# caffeine-hardware.net
KiCad netlist of a schematic drawn in EAGLE
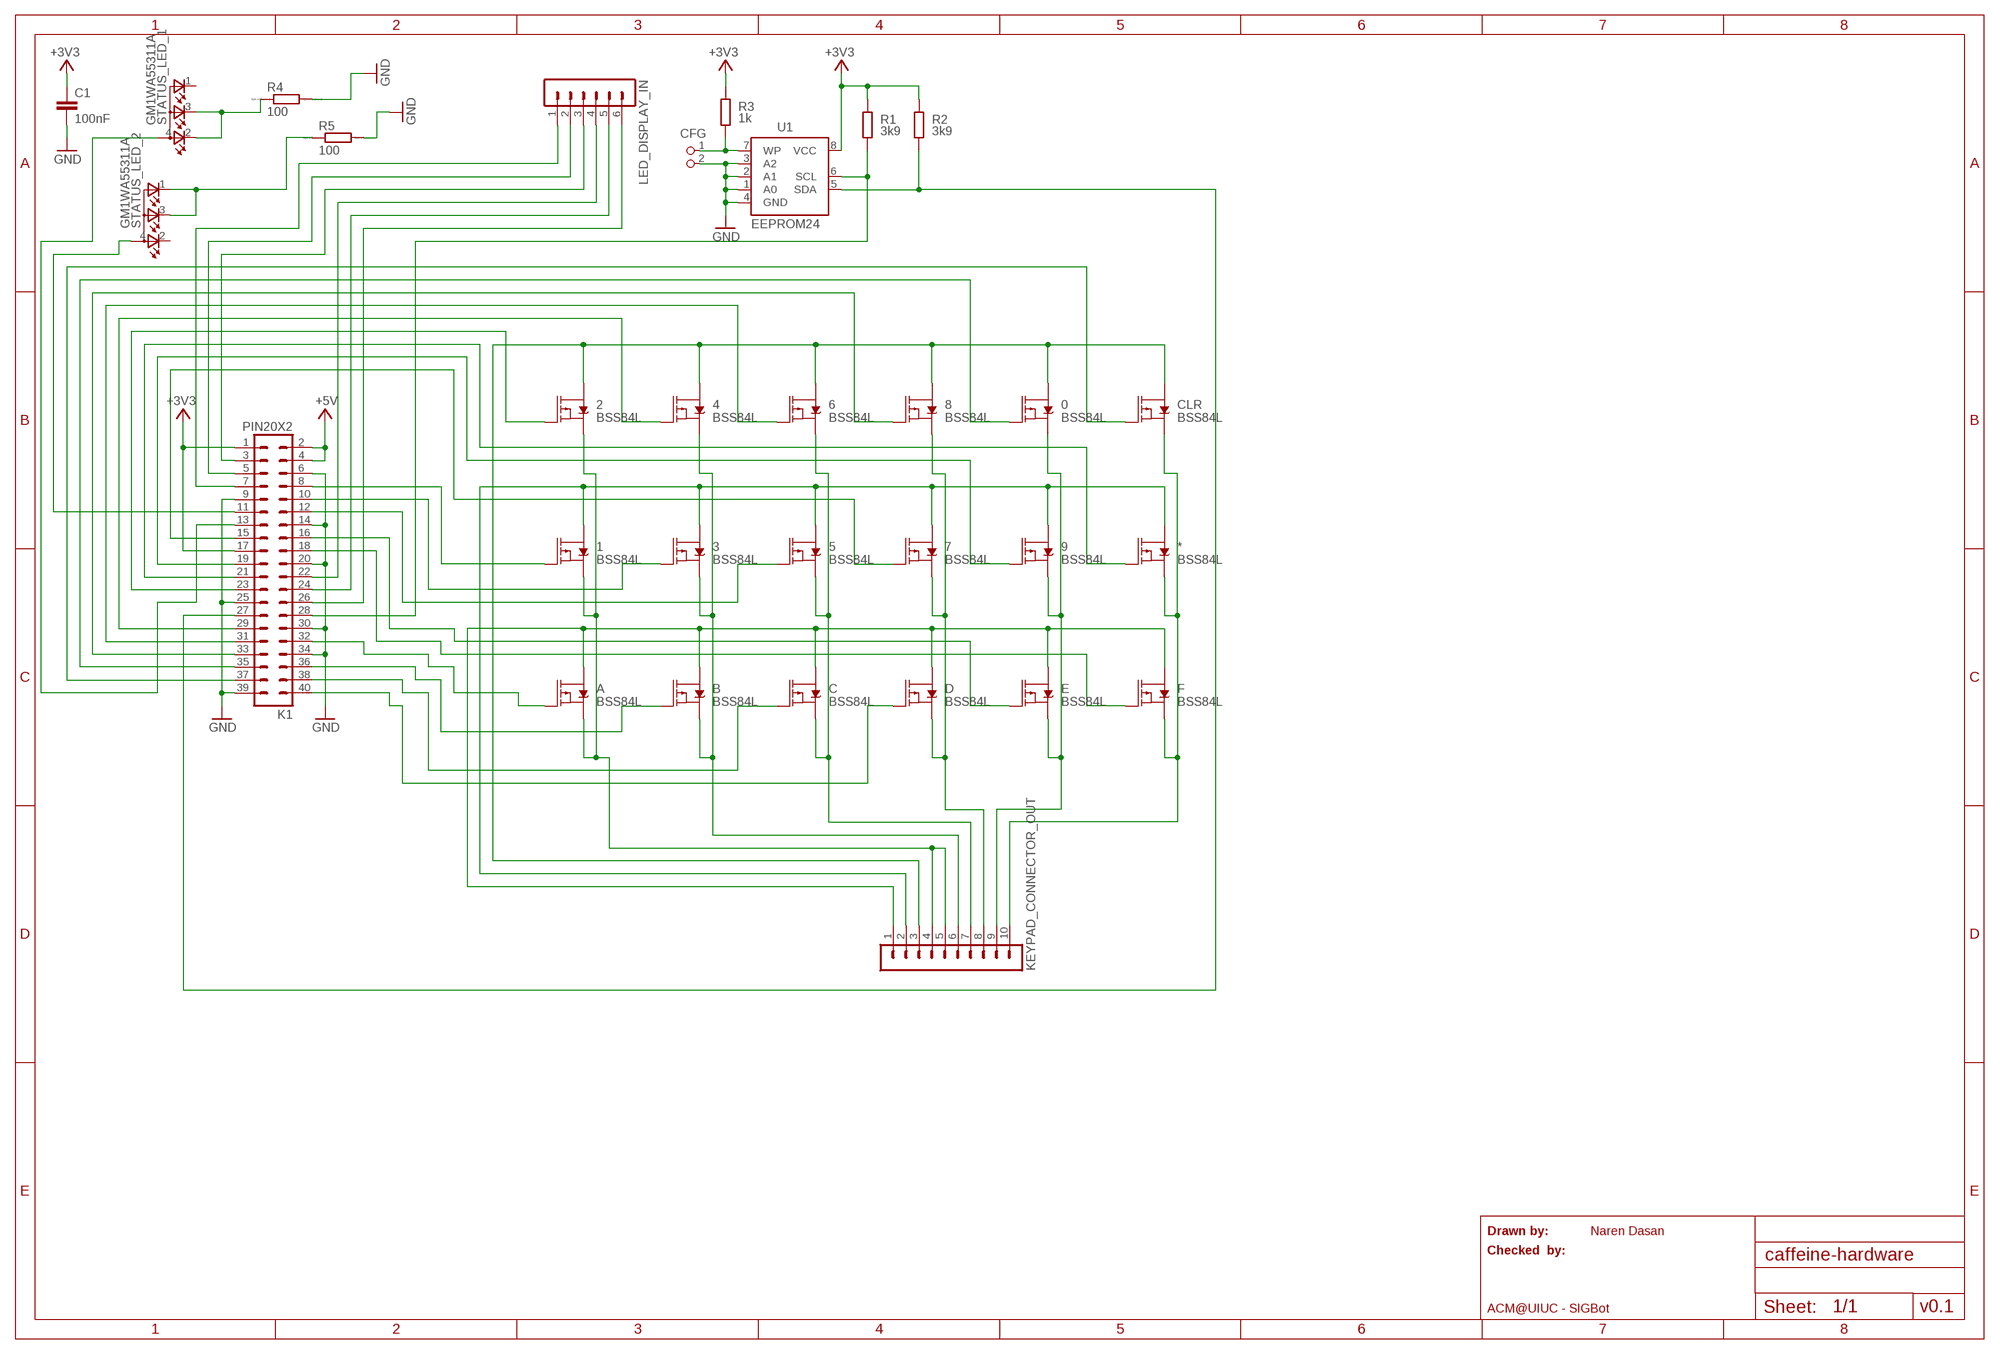
[diagram p0: schematic, sheet 1]

(export (version "E")
  (design (tool "Eeschema 10.0.6"))
  (components
    (comp (ref "*")
      (value "BSS84L")
      (footprint "eagle-import:SOT23-3")
      (libsource (lib "eagle-import") (part "MOSFET-PCH-SI2309DS"))
    )
    (comp (ref "0")
      (value "BSS84L")
      (footprint "eagle-import:SOT23-3")
      (libsource (lib "eagle-import") (part "MOSFET-PCH-SI2309DS"))
    )
    (comp (ref "1")
      (value "BSS84L")
      (footprint "eagle-import:SOT23-3")
      (libsource (lib "eagle-import") (part "MOSFET-PCH-SI2309DS"))
    )
    (comp (ref "2")
      (value "BSS84L")
      (footprint "eagle-import:SOT23-3")
      (libsource (lib "eagle-import") (part "MOSFET-PCH-SI2309DS"))
    )
    (comp (ref "3")
      (value "BSS84L")
      (footprint "eagle-import:SOT23-3")
      (libsource (lib "eagle-import") (part "MOSFET-PCH-SI2309DS"))
    )
    (comp (ref "4")
      (value "BSS84L")
      (footprint "eagle-import:SOT23-3")
      (libsource (lib "eagle-import") (part "MOSFET-PCH-SI2309DS"))
    )
    (comp (ref "5")
      (value "BSS84L")
      (footprint "eagle-import:SOT23-3")
      (libsource (lib "eagle-import") (part "MOSFET-PCH-SI2309DS"))
    )
    (comp (ref "6")
      (value "BSS84L")
      (footprint "eagle-import:SOT23-3")
      (libsource (lib "eagle-import") (part "MOSFET-PCH-SI2309DS"))
    )
    (comp (ref "7")
      (value "BSS84L")
      (footprint "eagle-import:SOT23-3")
      (libsource (lib "eagle-import") (part "MOSFET-PCH-SI2309DS"))
    )
    (comp (ref "8")
      (value "BSS84L")
      (footprint "eagle-import:SOT23-3")
      (libsource (lib "eagle-import") (part "MOSFET-PCH-SI2309DS"))
    )
    (comp (ref "9")
      (value "BSS84L")
      (footprint "eagle-import:SOT23-3")
      (libsource (lib "eagle-import") (part "MOSFET-PCH-SI2309DS"))
    )
    (comp (ref "A")
      (value "BSS84L")
      (footprint "eagle-import:SOT23-3")
      (libsource (lib "eagle-import") (part "MOSFET-PCH-SI2309DS"))
    )
    (comp (ref "B")
      (value "BSS84L")
      (footprint "eagle-import:SOT23-3")
      (libsource (lib "eagle-import") (part "MOSFET-PCH-SI2309DS"))
    )
    (comp (ref "C")
      (value "BSS84L")
      (footprint "eagle-import:SOT23-3")
      (libsource (lib "eagle-import") (part "MOSFET-PCH-SI2309DS"))
    )
    (comp (ref "C1")
      (value "100nF")
      (footprint "eagle-import:C0805K")
      (libsource (lib "eagle-import") (part "C-EUC0805K"))
    )
    (comp (ref "CFG")
      (value "PIN2_100")
      (footprint "eagle-import:PIN_W_2")
      (libsource (lib "eagle-import") (part "PIN2_100"))
    )
    (comp (ref "CLR")
      (value "BSS84L")
      (footprint "eagle-import:SOT23-3")
      (libsource (lib "eagle-import") (part "MOSFET-PCH-SI2309DS"))
    )
    (comp (ref "D")
      (value "BSS84L")
      (footprint "eagle-import:SOT23-3")
      (libsource (lib "eagle-import") (part "MOSFET-PCH-SI2309DS"))
    )
    (comp (ref "E")
      (value "BSS84L")
      (footprint "eagle-import:SOT23-3")
      (libsource (lib "eagle-import") (part "MOSFET-PCH-SI2309DS"))
    )
    (comp (ref "F")
      (value "BSS84L")
      (footprint "eagle-import:SOT23-3")
      (libsource (lib "eagle-import") (part "MOSFET-PCH-SI2309DS"))
    )
    (comp (ref "K1")
      (value "PIN20X2")
      (footprint "eagle-import:PIN_20X2")
      (libsource (lib "eagle-import") (part "PIN20X2"))
    )
    (comp (ref "KEYPAD_CONNECTOR_OUT")
      (value "MA10-1")
      (footprint "eagle-import:MA10-1")
      (libsource (lib "eagle-import") (part "MA10-1"))
    )
    (comp (ref "LED_DISPLAY_IN")
      (value "MA06-1")
      (footprint "eagle-import:MA06-1")
      (libsource (lib "eagle-import") (part "MA06-1"))
    )
    (comp (ref "R1")
      (value "3k9")
      (footprint "eagle-import:M0805")
      (fields (field (name "TOLERANCE") "5%"))
      (libsource (lib "eagle-import") (part "R-EU_M0805"))
    )
    (comp (ref "R2")
      (value "3k9")
      (footprint "eagle-import:M0805")
      (fields (field (name "TOLERANCE") "5%"))
      (libsource (lib "eagle-import") (part "R-EU_M0805"))
    )
    (comp (ref "R3")
      (value "1k")
      (footprint "eagle-import:M0805")
      (fields (field (name "TOLERANCE") "5%"))
      (libsource (lib "eagle-import") (part "R-EU_M0805"))
    )
    (comp (ref "R4")
      (value "100")
      (footprint "eagle-import:R0805")
      (libsource (lib "eagle-import") (part "R"))
    )
    (comp (ref "R5")
      (value "100")
      (footprint "eagle-import:R0805")
      (libsource (lib "eagle-import") (part "R"))
    )
    (comp (ref "STATUS_LED_1")
      (value "GM1WA55311A")
      (footprint "eagle-import:GM1WA55311A")
      (libsource (lib "eagle-import") (part "GM1WA55311A"))
    )
    (comp (ref "STATUS_LED_2")
      (value "GM1WA55311A")
      (footprint "eagle-import:GM1WA55311A")
      (libsource (lib "eagle-import") (part "GM1WA55311A"))
    )
    (comp (ref "U1")
      (value "EEPROM24")
      (footprint "eagle-import:SOIC8")
      (libsource (lib "eagle-import") (part "EEPROM24"))
    )
  )
  (nets
    (net (code "1") (name "+3V3") (class "Default")
      (node (ref "C1") (pin "1") (pinfunction "1_1") (pintype "passive"))
      (node (ref "K1") (pin "1") (pinfunction "1_1") (pintype "passive"))
      (node (ref "K1") (pin "17") (pinfunction "17_17") (pintype "passive"))
      (node (ref "R1") (pin "2") (pinfunction "2_2") (pintype "passive"))
      (node (ref "R2") (pin "2") (pinfunction "2_2") (pintype "passive"))
      (node (ref "R3") (pin "2") (pinfunction "2_2") (pintype "passive"))
      (node (ref "U1") (pin "8") (pinfunction "VCC_8") (pintype "power_in"))
    )
    (net (code "2") (name "+5V") (class "Default")
      (node (ref "K1") (pin "2") (pinfunction "2_2") (pintype "passive"))
      (node (ref "K1") (pin "4") (pinfunction "4_4") (pintype "passive"))
    )
    (net (code "3") (name "GND") (class "Default")
      (node (ref "C1") (pin "2") (pinfunction "2_2") (pintype "passive"))
      (node (ref "CFG") (pin "2") (pinfunction "2_2") (pintype "passive"))
      (node (ref "K1") (pin "14") (pinfunction "14_14") (pintype "passive"))
      (node (ref "K1") (pin "20") (pinfunction "20_20") (pintype "passive"))
      (node (ref "K1") (pin "25") (pinfunction "25_25") (pintype "passive"))
      (node (ref "K1") (pin "30") (pinfunction "30_30") (pintype "passive"))
      (node (ref "K1") (pin "34") (pinfunction "34_34") (pintype "passive"))
      (node (ref "K1") (pin "39") (pinfunction "39_39") (pintype "passive"))
      (node (ref "K1") (pin "6") (pinfunction "6_6") (pintype "passive"))
      (node (ref "K1") (pin "9") (pinfunction "9_9") (pintype "passive"))
      (node (ref "R4") (pin "2") (pinfunction "2_2") (pintype "passive"))
      (node (ref "R5") (pin "2") (pinfunction "2_2") (pintype "passive"))
      (node (ref "U1") (pin "1") (pinfunction "A0_1") (pintype "input"))
      (node (ref "U1") (pin "2") (pinfunction "A1_2") (pintype "input"))
      (node (ref "U1") (pin "3") (pinfunction "A2_3") (pintype "input"))
      (node (ref "U1") (pin "4") (pinfunction "GND_4") (pintype "power_in"))
    )
    (net (code "4") (name "Net-(*-D)") (class "Default")
      (node (ref "*") (pin "3") (pinfunction "D_3") (pintype "bidirectional"))
      (node (ref "1") (pin "3") (pinfunction "D_3") (pintype "bidirectional"))
      (node (ref "3") (pin "3") (pinfunction "D_3") (pintype "bidirectional"))
      (node (ref "5") (pin "3") (pinfunction "D_3") (pintype "bidirectional"))
      (node (ref "7") (pin "3") (pinfunction "D_3") (pintype "bidirectional"))
      (node (ref "9") (pin "3") (pinfunction "D_3") (pintype "bidirectional"))
      (node (ref "KEYPAD_CONNECTOR_OUT") (pin "2") (pinfunction "2_2") (pintype "passive"))
    )
    (net (code "5") (name "Net-(*-G)") (class "Default")
      (node (ref "*") (pin "1") (pinfunction "G_1") (pintype "bidirectional"))
      (node (ref "K1") (pin "21") (pinfunction "21_21") (pintype "passive"))
    )
    (net (code "6") (name "Net-(*-S)") (class "Default")
      (node (ref "*") (pin "2") (pinfunction "S_2") (pintype "bidirectional"))
      (node (ref "CLR") (pin "2") (pinfunction "S_2") (pintype "bidirectional"))
      (node (ref "F") (pin "2") (pinfunction "S_2") (pintype "bidirectional"))
      (node (ref "KEYPAD_CONNECTOR_OUT") (pin "10") (pinfunction "10_10") (pintype "passive"))
    )
    (net (code "7") (name "Net-(0-D)") (class "Default")
      (node (ref "0") (pin "3") (pinfunction "D_3") (pintype "bidirectional"))
      (node (ref "2") (pin "3") (pinfunction "D_3") (pintype "bidirectional"))
      (node (ref "4") (pin "3") (pinfunction "D_3") (pintype "bidirectional"))
      (node (ref "6") (pin "3") (pinfunction "D_3") (pintype "bidirectional"))
      (node (ref "8") (pin "3") (pinfunction "D_3") (pintype "bidirectional"))
      (node (ref "CLR") (pin "3") (pinfunction "D_3") (pintype "bidirectional"))
      (node (ref "KEYPAD_CONNECTOR_OUT") (pin "3") (pinfunction "3_3") (pintype "passive"))
    )
    (net (code "8") (name "Net-(0-G)") (class "Default")
      (node (ref "0") (pin "1") (pinfunction "G_1") (pintype "bidirectional"))
      (node (ref "K1") (pin "35") (pinfunction "35_35") (pintype "passive"))
    )
    (net (code "9") (name "Net-(0-S)") (class "Default")
      (node (ref "0") (pin "2") (pinfunction "S_2") (pintype "bidirectional"))
      (node (ref "9") (pin "2") (pinfunction "S_2") (pintype "bidirectional"))
      (node (ref "E") (pin "2") (pinfunction "S_2") (pintype "bidirectional"))
      (node (ref "KEYPAD_CONNECTOR_OUT") (pin "9") (pinfunction "9_9") (pintype "passive"))
    )
    (net (code "10") (name "Net-(1-G)") (class "Default")
      (node (ref "1") (pin "1") (pinfunction "G_1") (pintype "bidirectional"))
      (node (ref "K1") (pin "8") (pinfunction "8_8") (pintype "passive"))
    )
    (net (code "11") (name "Net-(1-S)") (class "Default")
      (node (ref "1") (pin "2") (pinfunction "S_2") (pintype "bidirectional"))
      (node (ref "2") (pin "2") (pinfunction "S_2") (pintype "bidirectional"))
      (node (ref "A") (pin "2") (pinfunction "S_2") (pintype "bidirectional"))
      (node (ref "KEYPAD_CONNECTOR_OUT") (pin "4") (pinfunction "4_4") (pintype "passive"))
      (node (ref "KEYPAD_CONNECTOR_OUT") (pin "5") (pinfunction "5_5") (pintype "passive"))
    )
    (net (code "12") (name "Net-(2-G)") (class "Default")
      (node (ref "2") (pin "1") (pinfunction "G_1") (pintype "bidirectional"))
      (node (ref "K1") (pin "23") (pinfunction "23_23") (pintype "passive"))
    )
    (net (code "13") (name "Net-(3-G)") (class "Default")
      (node (ref "3") (pin "1") (pinfunction "G_1") (pintype "bidirectional"))
      (node (ref "K1") (pin "10") (pinfunction "10_10") (pintype "passive"))
    )
    (net (code "14") (name "Net-(3-S)") (class "Default")
      (node (ref "3") (pin "2") (pinfunction "S_2") (pintype "bidirectional"))
      (node (ref "4") (pin "2") (pinfunction "S_2") (pintype "bidirectional"))
      (node (ref "B") (pin "2") (pinfunction "S_2") (pintype "bidirectional"))
      (node (ref "KEYPAD_CONNECTOR_OUT") (pin "6") (pinfunction "6_6") (pintype "passive"))
    )
    (net (code "15") (name "Net-(4-G)") (class "Default")
      (node (ref "4") (pin "1") (pinfunction "G_1") (pintype "bidirectional"))
      (node (ref "K1") (pin "29") (pinfunction "29_29") (pintype "passive"))
    )
    (net (code "16") (name "Net-(5-G)") (class "Default")
      (node (ref "5") (pin "1") (pinfunction "G_1") (pintype "bidirectional"))
      (node (ref "K1") (pin "12") (pinfunction "12_12") (pintype "passive"))
    )
    (net (code "17") (name "Net-(5-S)") (class "Default")
      (node (ref "5") (pin "2") (pinfunction "S_2") (pintype "bidirectional"))
      (node (ref "6") (pin "2") (pinfunction "S_2") (pintype "bidirectional"))
      (node (ref "C") (pin "2") (pinfunction "S_2") (pintype "bidirectional"))
      (node (ref "KEYPAD_CONNECTOR_OUT") (pin "7") (pinfunction "7_7") (pintype "passive"))
    )
    (net (code "18") (name "Net-(6-G)") (class "Default")
      (node (ref "6") (pin "1") (pinfunction "G_1") (pintype "bidirectional"))
      (node (ref "K1") (pin "31") (pinfunction "31_31") (pintype "passive"))
    )
    (net (code "19") (name "Net-(7-G)") (class "Default")
      (node (ref "7") (pin "1") (pinfunction "G_1") (pintype "bidirectional"))
      (node (ref "K1") (pin "15") (pinfunction "15_15") (pintype "passive"))
    )
    (net (code "20") (name "Net-(7-S)") (class "Default")
      (node (ref "7") (pin "2") (pinfunction "S_2") (pintype "bidirectional"))
      (node (ref "8") (pin "2") (pinfunction "S_2") (pintype "bidirectional"))
      (node (ref "D") (pin "2") (pinfunction "S_2") (pintype "bidirectional"))
      (node (ref "KEYPAD_CONNECTOR_OUT") (pin "8") (pinfunction "8_8") (pintype "passive"))
    )
    (net (code "21") (name "Net-(8-G)") (class "Default")
      (node (ref "8") (pin "1") (pinfunction "G_1") (pintype "bidirectional"))
      (node (ref "K1") (pin "33") (pinfunction "33_33") (pintype "passive"))
    )
    (net (code "22") (name "Net-(9-G)") (class "Default")
      (node (ref "9") (pin "1") (pinfunction "G_1") (pintype "bidirectional"))
      (node (ref "K1") (pin "19") (pinfunction "19_19") (pintype "passive"))
    )
    (net (code "23") (name "Net-(A-D)") (class "Default")
      (node (ref "A") (pin "3") (pinfunction "D_3") (pintype "bidirectional"))
      (node (ref "B") (pin "3") (pinfunction "D_3") (pintype "bidirectional"))
      (node (ref "C") (pin "3") (pinfunction "D_3") (pintype "bidirectional"))
      (node (ref "D") (pin "3") (pinfunction "D_3") (pintype "bidirectional"))
      (node (ref "E") (pin "3") (pinfunction "D_3") (pintype "bidirectional"))
      (node (ref "F") (pin "3") (pinfunction "D_3") (pintype "bidirectional"))
      (node (ref "KEYPAD_CONNECTOR_OUT") (pin "1") (pinfunction "1_1") (pintype "passive"))
    )
    (net (code "24") (name "Net-(A-G)") (class "Default")
      (node (ref "A") (pin "1") (pinfunction "G_1") (pintype "bidirectional"))
      (node (ref "K1") (pin "32") (pinfunction "32_32") (pintype "passive"))
    )
    (net (code "25") (name "Net-(B-G)") (class "Default")
      (node (ref "B") (pin "1") (pinfunction "G_1") (pintype "bidirectional"))
      (node (ref "K1") (pin "36") (pinfunction "36_36") (pintype "passive"))
    )
    (net (code "26") (name "Net-(C-G)") (class "Default")
      (node (ref "C") (pin "1") (pinfunction "G_1") (pintype "bidirectional"))
      (node (ref "K1") (pin "38") (pinfunction "38_38") (pintype "passive"))
    )
    (net (code "27") (name "Net-(CLR-G)") (class "Default")
      (node (ref "CLR") (pin "1") (pinfunction "G_1") (pintype "bidirectional"))
      (node (ref "K1") (pin "37") (pinfunction "37_37") (pintype "passive"))
    )
    (net (code "28") (name "Net-(D-G)") (class "Default")
      (node (ref "D") (pin "1") (pinfunction "G_1") (pintype "bidirectional"))
      (node (ref "K1") (pin "40") (pinfunction "40_40") (pintype "passive"))
    )
    (net (code "29") (name "Net-(E-G)") (class "Default")
      (node (ref "E") (pin "1") (pinfunction "G_1") (pintype "bidirectional"))
      (node (ref "K1") (pin "16") (pinfunction "16_16") (pintype "passive"))
    )
    (net (code "30") (name "Net-(F-G)") (class "Default")
      (node (ref "F") (pin "1") (pinfunction "G_1") (pintype "bidirectional"))
      (node (ref "K1") (pin "18") (pinfunction "18_18") (pintype "passive"))
    )
    (net (code "31") (name "Net-(K1-Pad3)") (class "Default")
      (node (ref "K1") (pin "3") (pinfunction "3_3") (pintype "passive"))
      (node (ref "LED_DISPLAY_IN") (pin "3") (pinfunction "3_3") (pintype "passive"))
    )
    (net (code "32") (name "Net-(K1-Pad5)") (class "Default")
      (node (ref "K1") (pin "5") (pinfunction "5_5") (pintype "passive"))
      (node (ref "LED_DISPLAY_IN") (pin "2") (pinfunction "2_2") (pintype "passive"))
    )
    (net (code "33") (name "Net-(K1-Pad7)") (class "Default")
      (node (ref "K1") (pin "7") (pinfunction "7_7") (pintype "passive"))
      (node (ref "LED_DISPLAY_IN") (pin "1") (pinfunction "1_1") (pintype "passive"))
    )
    (net (code "34") (name "Net-(K1-Pad22)") (class "Default")
      (node (ref "K1") (pin "22") (pinfunction "22_22") (pintype "passive"))
      (node (ref "LED_DISPLAY_IN") (pin "4") (pinfunction "4_4") (pintype "passive"))
    )
    (net (code "35") (name "Net-(K1-Pad24)") (class "Default")
      (node (ref "K1") (pin "24") (pinfunction "24_24") (pintype "passive"))
      (node (ref "LED_DISPLAY_IN") (pin "5") (pinfunction "5_5") (pintype "passive"))
    )
    (net (code "36") (name "Net-(K1-Pad26)") (class "Default")
      (node (ref "K1") (pin "26") (pinfunction "26_26") (pintype "passive"))
      (node (ref "LED_DISPLAY_IN") (pin "6") (pinfunction "6_6") (pintype "passive"))
    )
    (net (code "37") (name "Net-(STATUS_LED_1-A)") (class "Default")
      (node (ref "K1") (pin "13") (pinfunction "13_13") (pintype "passive"))
      (node (ref "STATUS_LED_1") (pin "4") (pinfunction "A_4") (pintype "passive"))
    )
    (net (code "38") (name "Net-(STATUS_LED_1-CBLUE)") (class "Default")
      (node (ref "R4") (pin "1") (pinfunction "1_1") (pintype "passive"))
      (node (ref "STATUS_LED_1") (pin "2") (pinfunction "CRED_2") (pintype "passive"))
      (node (ref "STATUS_LED_1") (pin "3") (pinfunction "CBLUE_3") (pintype "passive"))
    )
    (net (code "39") (name "Net-(STATUS_LED_2-A)") (class "Default")
      (node (ref "K1") (pin "11") (pinfunction "11_11") (pintype "passive"))
      (node (ref "STATUS_LED_2") (pin "4") (pinfunction "A_4") (pintype "passive"))
    )
    (net (code "40") (name "Net-(STATUS_LED_2-CBLUE)") (class "Default")
      (node (ref "R5") (pin "1") (pinfunction "1_1") (pintype "passive"))
      (node (ref "STATUS_LED_2") (pin "1") (pinfunction "CGREEN_1") (pintype "passive"))
      (node (ref "STATUS_LED_2") (pin "3") (pinfunction "CBLUE_3") (pintype "passive"))
    )
    (net (code "41") (name "Net-(U1-SCL)") (class "Default")
      (node (ref "K1") (pin "28") (pinfunction "28_28") (pintype "passive"))
      (node (ref "R1") (pin "1") (pinfunction "1_1") (pintype "passive"))
      (node (ref "U1") (pin "6") (pinfunction "SCL_6") (pintype "input"))
    )
    (net (code "42") (name "Net-(U1-SDA)") (class "Default")
      (node (ref "K1") (pin "27") (pinfunction "27_27") (pintype "passive"))
      (node (ref "R2") (pin "1") (pinfunction "1_1") (pintype "passive"))
      (node (ref "U1") (pin "5") (pinfunction "SDA_5") (pintype "bidirectional"))
    )
    (net (code "43") (name "Net-(U1-WP)") (class "Default")
      (node (ref "CFG") (pin "1") (pinfunction "1_1") (pintype "passive"))
      (node (ref "R3") (pin "1") (pinfunction "1_1") (pintype "passive"))
      (node (ref "U1") (pin "7") (pinfunction "WP_7") (pintype "input"))
    )
    (net (code "44") (name "unconnected-(STATUS_LED_1-CGREEN-Pad1)") (class "Default")
      (node (ref "STATUS_LED_1") (pin "1") (pinfunction "CGREEN_1") (pintype "passive"))
    )
    (net (code "45") (name "unconnected-(STATUS_LED_2-CRED-Pad2)") (class "Default")
      (node (ref "STATUS_LED_2") (pin "2") (pinfunction "CRED_2") (pintype "passive"))
    )
  )
)
